# Data_Connector.net
KiCad netlist of a schematic drawn in Altium Designer
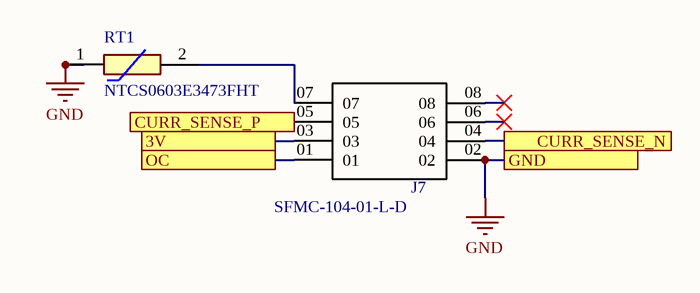
[diagram p0: Data Connector.SchDoc]

(export (version "E")
  (design (tool "Eeschema 10.0.6"))
  (components
    (comp (ref "J7")
      (value "SFMC-104-01-L-D")
      (footprint "*SAMTEC_SFMC-104-01-L-D_SFMC-104-01-L-D(Primary)")
      (libsource (lib "Schlib1") (part "SFMC-104-01-L-D"))
    )
    (comp (ref "RT1")
      (value "NTCS0603E3473FHT")
      (footprint "SamacSys:THRMC1608X95N")
      (description "Thermistor")
      (fields (field (name "MOUSER PART NUMBER") "594-NTCS0603E3473FHT"))
      (libsource (lib "*") (part "NTCS0603E3473FHT"))
    )
  )
  (nets
    (net (code "1") (name "/3V") (class "Default")
      (node (ref "J7") (pin "03") (pinfunction "03_03") (pintype "passive"))
    )
    (net (code "2") (name "/CURR_SENSE_N") (class "Default")
      (node (ref "J7") (pin "04") (pinfunction "04_04") (pintype "passive"))
    )
    (net (code "3") (name "/CURR_SENSE_P") (class "Default")
      (node (ref "J7") (pin "05") (pinfunction "05_05") (pintype "passive"))
    )
    (net (code "4") (name "/OC") (class "Default")
      (node (ref "J7") (pin "01") (pinfunction "01_01") (pintype "passive"))
    )
    (net (code "5") (name "GND") (class "Default")
      (node (ref "J7") (pin "02") (pinfunction "02_02") (pintype "passive"))
      (node (ref "RT1") (pin "1") (pinfunction "1_1") (pintype "passive"))
    )
    (net (code "6") (name "Net-(J7-Pad07)") (class "Default")
      (node (ref "J7") (pin "07") (pinfunction "07_07") (pintype "passive"))
      (node (ref "RT1") (pin "2") (pinfunction "2_2") (pintype "passive"))
    )
    (net (code "7") (name "unconnected-(J7-Pad06)") (class "Default")
      (node (ref "J7") (pin "06") (pinfunction "06_06") (pintype "passive+no_connect"))
    )
    (net (code "8") (name "unconnected-(J7-Pad08)") (class "Default")
      (node (ref "J7") (pin "08") (pinfunction "08_08") (pintype "passive+no_connect"))
    )
  )
)
